# main.net
KiCad netlist of a schematic drawn in Altium Designer
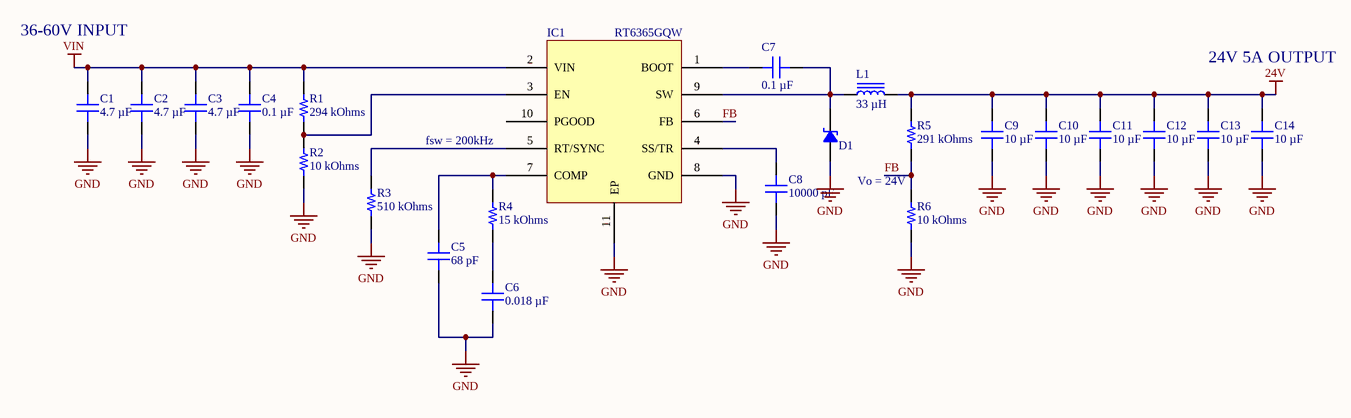
[diagram p0: main.SchDoc]

(export (version "E")
  (design (tool "Eeschema 10.0.6"))
  (components
    (comp (ref "C1")
      (value "4.7 µF")
      (footprint "CAP 1206_3216 - 0.8MM")
      (description "CAP CER 4.7UF 100V X7R 1206")
      (fields
        (field (name "PART NUMBER") "GRM31CZ72A475KE11L")
        (field (name "MANUFACTURER") "Murata Electronics")
      )
      (libsource (lib "Celestial Altium Library - altium_library") (part "Capacitor"))
    )
    (comp (ref "C2")
      (value "4.7 µF")
      (footprint "CAP 1206_3216 - 0.8MM")
      (description "CAP CER 4.7UF 100V X7R 1206")
      (fields
        (field (name "PART NUMBER") "GRM31CZ72A475KE11L")
        (field (name "MANUFACTURER") "Murata Electronics")
      )
      (libsource (lib "Celestial Altium Library - altium_library") (part "Capacitor"))
    )
    (comp (ref "C3")
      (value "4.7 µF")
      (footprint "CAP 1206_3216 - 0.8MM")
      (description "CAP CER 4.7UF 100V X7R 1206")
      (fields
        (field (name "PART NUMBER") "GRM31CZ72A475KE11L")
        (field (name "MANUFACTURER") "Murata Electronics")
      )
      (libsource (lib "Celestial Altium Library - altium_library") (part "Capacitor"))
    )
    (comp (ref "C4")
      (value "0.1 µF")
      (footprint "CAP 0603_1608")
      (description "CAP CER 0.1UF 100V X7R 0603")
      (fields
        (field (name "PART NUMBER") "CL10B104KC8NNNC")
        (field (name "MANUFACTURER") "Samsung Electro-Mechanics")
      )
      (libsource (lib "Celestial Altium Library - altium_library") (part "Capacitor"))
    )
    (comp (ref "C5")
      (value "68 pF")
      (footprint "CAP 0603_1608")
      (description "CAP CER 68PF 50V C0G/NP0 0603")
      (fields
        (field (name "PART NUMBER") "CL10C680JB8NNNC")
        (field (name "MANUFACTURER") "Samsung Electro-Mechanics")
      )
      (libsource (lib "Celestial Altium Library - altium_library") (part "Capacitor"))
    )
    (comp (ref "C6")
      (value "0.018 µF")
      (footprint "CAP 0603_1608")
      (description "CAP CER 0.018UF 25V X7R 0603")
      (fields (field (name "PART NUMBER") "CC0603JRX7R8BB183") (field (name "MANUFACTURER") "Yageo"))
      (libsource (lib "Celestial Altium Library - altium_library") (part "Capacitor"))
    )
    (comp (ref "C7")
      (value "0.1 µF")
      (footprint "CAP 0603_1608")
      (description "CAP CER 0.1UF 100V X7R 0603")
      (fields
        (field (name "PART NUMBER") "CL10B104KC8NNNC")
        (field (name "MANUFACTURER") "Samsung Electro-Mechanics")
      )
      (libsource (lib "Celestial Altium Library - altium_library") (part "Capacitor"))
    )
    (comp (ref "C8")
      (value "10000 pF")
      (footprint "CAP 0603_1608")
      (description "CAP CER 10000PF 50V X7R 0603")
      (fields
        (field (name "PART NUMBER") "CL10B103KB8NNNC")
        (field (name "MANUFACTURER") "Samsung Electro-Mechanics")
      )
      (libsource (lib "Celestial Altium Library - altium_library") (part "Capacitor"))
    )
    (comp (ref "C9")
      (value "10 µF")
      (footprint "CAP 1206_3216 - 0.8MM")
      (description "CAP CER 10UF 50V X7R 1206")
      (fields
        (field (name "PART NUMBER") "CL31B106KBHNNNE")
        (field (name "MANUFACTURER") "Samsung Electro-Mechanics")
      )
      (libsource (lib "Celestial Altium Library - altium_library") (part "Capacitor"))
    )
    (comp (ref "C10")
      (value "10 µF")
      (footprint "CAP 1206_3216 - 0.8MM")
      (description "CAP CER 10UF 50V X7R 1206")
      (fields
        (field (name "PART NUMBER") "CL31B106KBHNNNE")
        (field (name "MANUFACTURER") "Samsung Electro-Mechanics")
      )
      (libsource (lib "Celestial Altium Library - altium_library") (part "Capacitor"))
    )
    (comp (ref "C11")
      (value "10 µF")
      (footprint "CAP 1206_3216 - 0.8MM")
      (description "CAP CER 10UF 50V X7R 1206")
      (fields
        (field (name "PART NUMBER") "CL31B106KBHNNNE")
        (field (name "MANUFACTURER") "Samsung Electro-Mechanics")
      )
      (libsource (lib "Celestial Altium Library - altium_library") (part "Capacitor"))
    )
    (comp (ref "C12")
      (value "10 µF")
      (footprint "CAP 1206_3216 - 0.8MM")
      (description "CAP CER 10UF 50V X7R 1206")
      (fields
        (field (name "PART NUMBER") "CL31B106KBHNNNE")
        (field (name "MANUFACTURER") "Samsung Electro-Mechanics")
      )
      (libsource (lib "Celestial Altium Library - altium_library") (part "Capacitor"))
    )
    (comp (ref "C13")
      (value "10 µF")
      (footprint "CAP 1206_3216 - 0.8MM")
      (description "CAP CER 10UF 50V X7R 1206")
      (fields
        (field (name "PART NUMBER") "CL31B106KBHNNNE")
        (field (name "MANUFACTURER") "Samsung Electro-Mechanics")
      )
      (libsource (lib "Celestial Altium Library - altium_library") (part "Capacitor"))
    )
    (comp (ref "C14")
      (value "10 µF")
      (footprint "CAP 1206_3216 - 0.8MM")
      (description "CAP CER 10UF 50V X7R 1206")
      (fields
        (field (name "PART NUMBER") "CL31B106KBHNNNE")
        (field (name "MANUFACTURER") "Samsung Electro-Mechanics")
      )
      (libsource (lib "Celestial Altium Library - altium_library") (part "Capacitor"))
    )
    (comp (ref "D1")
      (value "DIODE SCHOTTKY 60V 10A TO277B")
      (footprint "TO-277B:SVM1060XB_R2_00001")
      (description "Diode 60 V 10A Surface Mount TO-277B")
      (libsource (lib "SVM1060XB") (part "SVM1060XB_R2_00001"))
    )
    (comp (ref "IC1")
      (value "RT6365GQW")
      (footprint "10-WDFN(4x4):RT6365GQW")
      (description "IC REG BUCK ADJ 5A 10WDFN")
      (libsource (lib "RT6365GQW") (part "RT6365GQW"))
    )
    (comp (ref "L1")
      (value "33 µH")
      (footprint "SRP1265A")
      (description "FIXED IND 33UH 4.2A 45 MOHM SMD")
      (fields (field (name "PART NUMBER") "7447709330") (field (name "MANUFACTURER") "Würth Elektronik"))
      (libsource (lib "Celestial Altium Library - altium_library") (part "Inductor"))
    )
    (comp (ref "R1")
      (value "294 kOhms")
      (footprint "RES 0603_1608")
      (description "RES 294K OHM 1% 1/10W 0603")
      (fields (field (name "PART NUMBER") "RC0603FR-07294KL") (field (name "MANUFACTURER") "Yageo"))
      (libsource (lib "Celestial Altium Library - altium_library") (part "Resistor"))
    )
    (comp (ref "R2")
      (value "10 kOhms")
      (footprint "RES 0603_1608")
      (description "RES 10K OHM 1% 1/10W 0603")
      (fields (field (name "PART NUMBER") "RC0603FR-0710KL") (field (name "MANUFACTURER") "Yageo"))
      (libsource (lib "Celestial Altium Library - altium_library") (part "Resistor"))
    )
    (comp (ref "R3")
      (value "510 kOhms")
      (footprint "RES 0603_1608")
      (description "RES 510K OHM 1% 1/10W 0603")
      (fields (field (name "PART NUMBER") "RC0603FR-07510KL") (field (name "MANUFACTURER") "Yageo"))
      (libsource (lib "Celestial Altium Library - altium_library") (part "Resistor"))
    )
    (comp (ref "R4")
      (value "15 kOhms")
      (footprint "RES 0603_1608")
      (description "RES SMD 15K OHM 1% 1/10W 0603")
      (fields (field (name "PART NUMBER") "AC0603FR-0715KL") (field (name "MANUFACTURER") "Yageo"))
      (libsource (lib "Celestial Altium Library - altium_library") (part "Resistor"))
    )
    (comp (ref "R5")
      (value "291 kOhms")
      (footprint "RES 0603_1608")
      (description "RES 291K OHM 1% 1/10W 0603")
      (fields
        (field (name "PART NUMBER") "RN73R1JTTD2913F100")
        (field (name "MANUFACTURER") "KOA Speer Electronics, Inc.")
      )
      (libsource (lib "Celestial Altium Library - altium_library") (part "Resistor"))
    )
    (comp (ref "R6")
      (value "10 kOhms")
      (footprint "RES 0603_1608")
      (description "RES 10K OHM 1% 1/10W 0603")
      (fields (field (name "PART NUMBER") "RC0603FR-0710KL") (field (name "MANUFACTURER") "Yageo"))
      (libsource (lib "Celestial Altium Library - altium_library") (part "Resistor"))
    )
  )
  (nets
    (net (code "1") (name "/FB") (class "Default")
      (node (ref "IC1") (pin "6") (pinfunction "FB_6") (pintype "passive"))
      (node (ref "R5") (pin "1") (pinfunction "1_1") (pintype "passive"))
      (node (ref "R6") (pin "2") (pinfunction "2_2") (pintype "passive"))
    )
    (net (code "2") (name "24V") (class "Default")
      (node (ref "C10") (pin "2") (pinfunction "2_2") (pintype "passive"))
      (node (ref "C11") (pin "2") (pinfunction "2_2") (pintype "passive"))
      (node (ref "C12") (pin "2") (pinfunction "2_2") (pintype "passive"))
      (node (ref "C13") (pin "2") (pinfunction "2_2") (pintype "passive"))
      (node (ref "C14") (pin "2") (pinfunction "2_2") (pintype "passive"))
      (node (ref "C9") (pin "2") (pinfunction "2_2") (pintype "passive"))
      (node (ref "L1") (pin "2") (pinfunction "2_2") (pintype "passive"))
      (node (ref "R5") (pin "2") (pinfunction "2_2") (pintype "passive"))
    )
    (net (code "3") (name "GND") (class "Default")
      (node (ref "C1") (pin "1") (pinfunction "1_1") (pintype "passive"))
      (node (ref "C10") (pin "1") (pinfunction "1_1") (pintype "passive"))
      (node (ref "C11") (pin "1") (pinfunction "1_1") (pintype "passive"))
      (node (ref "C12") (pin "1") (pinfunction "1_1") (pintype "passive"))
      (node (ref "C13") (pin "1") (pinfunction "1_1") (pintype "passive"))
      (node (ref "C14") (pin "1") (pinfunction "1_1") (pintype "passive"))
      (node (ref "C2") (pin "1") (pinfunction "1_1") (pintype "passive"))
      (node (ref "C3") (pin "1") (pinfunction "1_1") (pintype "passive"))
      (node (ref "C4") (pin "1") (pinfunction "1_1") (pintype "passive"))
      (node (ref "C5") (pin "1") (pinfunction "1_1") (pintype "passive"))
      (node (ref "C6") (pin "1") (pinfunction "1_1") (pintype "passive"))
      (node (ref "C8") (pin "1") (pinfunction "1_1") (pintype "passive"))
      (node (ref "C9") (pin "1") (pinfunction "1_1") (pintype "passive"))
      (node (ref "D1") (pin "1") (pinfunction "Anode_1") (pintype "passive"))
      (node (ref "IC1") (pin "11") (pinfunction "EP_11") (pintype "passive"))
      (node (ref "IC1") (pin "8") (pinfunction "GND_8") (pintype "passive"))
      (node (ref "R2") (pin "1") (pinfunction "1_1") (pintype "passive"))
      (node (ref "R3") (pin "1") (pinfunction "1_1") (pintype "passive"))
      (node (ref "R6") (pin "1") (pinfunction "1_1") (pintype "passive"))
    )
    (net (code "4") (name "Net-(C6-Pad2)") (class "Default")
      (node (ref "C6") (pin "2") (pinfunction "2_2") (pintype "passive"))
      (node (ref "R4") (pin "1") (pinfunction "1_1") (pintype "passive"))
    )
    (net (code "5") (name "Net-(D1-Cathode)") (class "Default")
      (node (ref "C7") (pin "1") (pinfunction "1_1") (pintype "passive"))
      (node (ref "D1") (pin "2") (pinfunction "Cathode_2") (pintype "passive"))
      (node (ref "IC1") (pin "9") (pinfunction "SW_9") (pintype "passive"))
      (node (ref "L1") (pin "1") (pinfunction "1_1") (pintype "passive"))
    )
    (net (code "6") (name "Net-(IC1-BOOT)") (class "Default")
      (node (ref "C7") (pin "2") (pinfunction "2_2") (pintype "passive"))
      (node (ref "IC1") (pin "1") (pinfunction "BOOT_1") (pintype "passive"))
    )
    (net (code "7") (name "Net-(IC1-COMP)") (class "Default")
      (node (ref "C5") (pin "2") (pinfunction "2_2") (pintype "passive"))
      (node (ref "IC1") (pin "7") (pinfunction "COMP_7") (pintype "passive"))
      (node (ref "R4") (pin "2") (pinfunction "2_2") (pintype "passive"))
    )
    (net (code "8") (name "Net-(IC1-EN)") (class "Default")
      (node (ref "IC1") (pin "3") (pinfunction "EN_3") (pintype "passive"))
      (node (ref "R1") (pin "1") (pinfunction "1_1") (pintype "passive"))
      (node (ref "R2") (pin "2") (pinfunction "2_2") (pintype "passive"))
    )
    (net (code "9") (name "Net-(IC1-RT{slash}SYNC)") (class "Default")
      (node (ref "IC1") (pin "5") (pinfunction "RT/SYNC_5") (pintype "passive"))
      (node (ref "R3") (pin "2") (pinfunction "2_2") (pintype "passive"))
    )
    (net (code "10") (name "Net-(IC1-SS{slash}TR)") (class "Default")
      (node (ref "C8") (pin "2") (pinfunction "2_2") (pintype "passive"))
      (node (ref "IC1") (pin "4") (pinfunction "SS/TR_4") (pintype "passive"))
    )
    (net (code "11") (name "VIN") (class "Default")
      (node (ref "C1") (pin "2") (pinfunction "2_2") (pintype "passive"))
      (node (ref "C2") (pin "2") (pinfunction "2_2") (pintype "passive"))
      (node (ref "C3") (pin "2") (pinfunction "2_2") (pintype "passive"))
      (node (ref "C4") (pin "2") (pinfunction "2_2") (pintype "passive"))
      (node (ref "IC1") (pin "2") (pinfunction "VIN_2") (pintype "passive"))
      (node (ref "R1") (pin "2") (pinfunction "2_2") (pintype "passive"))
    )
    (net (code "12") (name "unconnected-(IC1-PGOOD-Pad10)") (class "Default")
      (node (ref "IC1") (pin "10") (pinfunction "PGOOD_10") (pintype "passive"))
    )
  )
)
